# Switcher_Charger.net
KiCad netlist of a schematic drawn in Altium Designer
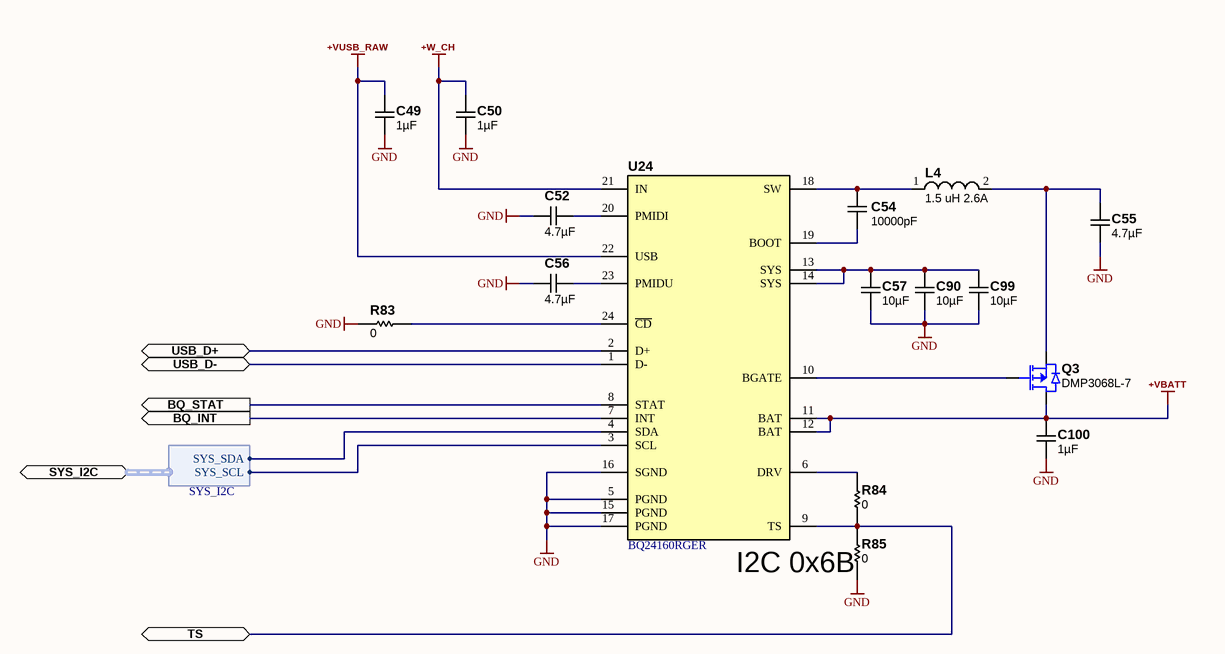
[diagram p0: Switcher_Charger.SchDoc]

(export (version "E")
  (design (tool "Eeschema 10.0.6"))
  (components
    (comp (ref "C49")
      (value "1µF")
      (footprint "C0603_0.90MM_MD")
      (description "CAP CER 1UF 16V X7R 0603")
      (fields
        (field (name "MANUFACTURER PART NUMBER") "CGA3E1X7R1C105K080AC")
        (field (name "MANUFACTURER") "TDK Corporation")
      )
      (libsource (lib "Capacitors - TDK- AEC-Q200") (part "C_2P_NP"))
    )
    (comp (ref "C50")
      (value "1µF")
      (footprint "C0603_0.90MM_MD")
      (description "CAP CER 1UF 16V X7R 0603")
      (fields
        (field (name "MANUFACTURER PART NUMBER") "CGA3E1X7R1C105K080AC")
        (field (name "MANUFACTURER") "TDK Corporation")
      )
      (libsource (lib "Capacitors - TDK- AEC-Q200") (part "C_2P_NP"))
    )
    (comp (ref "C52")
      (value "4.7µF")
      (footprint "C0805_1.45MM_MD")
      (description "CAP CER 4.7UF 16V X7R 0805")
      (fields
        (field (name "MANUFACTURER PART NUMBER") "CGA4J3X7R1C475K125AB")
        (field (name "MANUFACTURER") "TDK Corporation")
      )
      (libsource (lib "Capacitors - TDK- AEC-Q200") (part "C_2P_NP"))
    )
    (comp (ref "C54")
      (value "10000pF")
      (footprint "C0603_0.90MM_MD")
      (description "CAP CER 10000PF 50V C0G 0603")
      (fields
        (field (name "MANUFACTURER PART NUMBER") "CGA3E2C0G1H103J080AA")
        (field (name "MANUFACTURER") "TDK Corporation")
      )
      (libsource (lib "Capacitors - TDK- AEC-Q200") (part "C_2P_NP"))
    )
    (comp (ref "C55")
      (value "4.7µF")
      (footprint "C0805_1.45MM_MD")
      (description "CAP CER 4.7UF 16V X7R 0805")
      (fields
        (field (name "MANUFACTURER PART NUMBER") "CGA4J3X7R1C475K125AB")
        (field (name "MANUFACTURER") "TDK Corporation")
      )
      (libsource (lib "Capacitors - TDK- AEC-Q200") (part "C_2P_NP"))
    )
    (comp (ref "C56")
      (value "4.7µF")
      (footprint "C0805_1.45MM_MD")
      (description "CAP CER 4.7UF 16V X7R 0805")
      (fields
        (field (name "MANUFACTURER PART NUMBER") "CGA4J3X7R1C475K125AB")
        (field (name "MANUFACTURER") "TDK Corporation")
      )
      (libsource (lib "Capacitors - TDK- AEC-Q200") (part "C_2P_NP"))
    )
    (comp (ref "C57")
      (value "10µF")
      (footprint "C0805_1.40MM_MD")
      (description "CAP CER 10UF 10V X7R 0805")
      (fields
        (field (name "MANUFACTURER PART NUMBER") "GCM21BR71A106KE22L")
        (field (name "MANUFACTURER") "Murata Electronics")
      )
      (libsource (lib "Capacitors - Murata - AEC-Q200") (part "C_2P_NP"))
    )
    (comp (ref "C90")
      (value "10µF")
      (footprint "C0805_1.40MM_MD")
      (description "CAP CER 10UF 10V X7R 0805")
      (fields
        (field (name "MANUFACTURER PART NUMBER") "GCM21BR71A106KE22L")
        (field (name "MANUFACTURER") "Murata Electronics")
      )
      (libsource (lib "Capacitors - Murata - AEC-Q200") (part "C_2P_NP"))
    )
    (comp (ref "C99")
      (value "10µF")
      (footprint "C0805_1.40MM_MD")
      (description "CAP CER 10UF 10V X7R 0805")
      (fields
        (field (name "MANUFACTURER PART NUMBER") "GCM21BR71A106KE22L")
        (field (name "MANUFACTURER") "Murata Electronics")
      )
      (libsource (lib "Capacitors - Murata - AEC-Q200") (part "C_2P_NP"))
    )
    (comp (ref "C100")
      (value "1µF")
      (footprint "C0603_0.90MM_MD")
      (description "CAP CER 1UF 16V X7R 0603")
      (fields
        (field (name "MANUFACTURER PART NUMBER") "CGA3E1X7R1C105K080AC")
        (field (name "MANUFACTURER") "TDK Corporation")
      )
      (libsource (lib "Capacitors - TDK- AEC-Q200") (part "C_2P_NP"))
    )
    (comp (ref "L4")
      (value "1.5 uH 2.6A")
      (footprint "L_DO1608C")
      (fields
        (field (name "MANUFACTURER PART NUMBER") "DO1608C-152ML")
        (field (name "MANUFACTURER") "Coilcraft")
        (field (name "PART NUMBER") "DO1608C-152ML_")
      )
      (libsource (lib "Inductors") (part "L_2P"))
    )
    (comp (ref "Q3")
      (value "DMP3068L-7")
      (footprint "SOT-23")
      (description "MOSFET P-CH 30V 3.9A SOT23")
      (fields (field (name "MANUFACTURER") "Diodes"))
      (libsource (lib "eTransistor") (part "DMP3068L-7"))
    )
    (comp (ref "R83")
      (value "0")
      (footprint "R0603_0.55MM_MD")
      (description "RES 0.0 OHM 1/10W JUMP 0603 SMD")
      (fields
        (field (name "MANUFACTURER PART NUMBER") "ERJ-3GEY0R00V")
        (field (name "MANUFACTURER") "Panasonic Electronic Components")
      )
      (libsource (lib "Resistors - Panasonic - AEC-Q200") (part "R_2P"))
    )
    (comp (ref "R84")
      (value "0")
      (footprint "R0603_0.55MM_MD")
      (description "RES 0.0 OHM 1/10W JUMP 0603 SMD")
      (fields
        (field (name "MANUFACTURER PART NUMBER") "ERJ-3GEY0R00V")
        (field (name "MANUFACTURER") "Panasonic Electronic Components")
      )
      (libsource (lib "Resistors - Panasonic - AEC-Q200") (part "R_2P"))
    )
    (comp (ref "R85")
      (value "0")
      (footprint "R0603_0.55MM_MD")
      (description "RES 0.0 OHM 1/10W JUMP 0603 SMD")
      (fields
        (field (name "MANUFACTURER PART NUMBER") "ERJ-3GEY0R00V")
        (field (name "MANUFACTURER") "Panasonic Electronic Components")
      )
      (libsource (lib "Resistors - Panasonic - AEC-Q200") (part "R_2P"))
    )
    (comp (ref "U24")
      (value "BQ24160RGER")
      (footprint "QFN50P400X400X100_HS-25N")
      (description "Switching Battery Charger Li-Ion 2500mA 3.5V to 4.44V 24-Pin VQFN EP T/R")
      (fields (field (name "MANUFACTURER") "Texas Instruments"))
      (libsource (lib "eIC_BatteryManagement") (part "BQ24160RGER"))
    )
  )
  (nets
    (net (code "2") (name "+VBATT") (class "Default")
      (node (ref "C100") (pin "2") (pinfunction "1_2") (pintype "passive"))
      (node (ref "Q3") (pin "3") (pinfunction "D_3") (pintype "passive"))
      (node (ref "U24") (pin "11") (pinfunction "BAT_11") (pintype "passive"))
      (node (ref "U24") (pin "12") (pinfunction "BAT_12") (pintype "passive"))
    )
    (net (code "3") (name "+VUSB_RAW") (class "Default")
      (node (ref "C49") (pin "2") (pinfunction "1_2") (pintype "passive"))
      (node (ref "U24") (pin "22") (pinfunction "USB_22") (pintype "passive"))
    )
    (net (code "4") (name "+W_CH") (class "Default")
      (node (ref "C50") (pin "2") (pinfunction "1_2") (pintype "passive"))
      (node (ref "U24") (pin "21") (pinfunction "IN_21") (pintype "passive"))
    )
    (net (code "5") (name "/BQ_INT") (class "Default")
      (node (ref "U24") (pin "7") (pinfunction "INT_7") (pintype "passive"))
    )
    (net (code "6") (name "/BQ_STAT") (class "Default")
      (node (ref "U24") (pin "8") (pinfunction "STAT_8") (pintype "passive"))
    )
    (net (code "7") (name "/SYS_SCL") (class "Default")
      (node (ref "U24") (pin "3") (pinfunction "SCL_3") (pintype "passive"))
    )
    (net (code "8") (name "/SYS_SDA") (class "Default")
      (node (ref "U24") (pin "4") (pinfunction "SDA_4") (pintype "passive"))
    )
    (net (code "9") (name "/TS") (class "Default")
      (node (ref "R84") (pin "1") (pinfunction "1_1") (pintype "passive"))
      (node (ref "R85") (pin "2") (pinfunction "2_2") (pintype "passive"))
      (node (ref "U24") (pin "9") (pinfunction "TS_9") (pintype "passive"))
    )
    (net (code "10") (name "/USB_D+") (class "Default")
      (node (ref "U24") (pin "2") (pinfunction "D+_2") (pintype "passive"))
    )
    (net (code "11") (name "/USB_D-") (class "Default")
      (node (ref "U24") (pin "1") (pinfunction "D-_1") (pintype "passive"))
    )
    (net (code "13") (name "GND") (class "Default")
      (node (ref "C100") (pin "1") (pinfunction "1_1") (pintype "passive"))
      (node (ref "C49") (pin "1") (pinfunction "1_1") (pintype "passive"))
      (node (ref "C50") (pin "1") (pinfunction "1_1") (pintype "passive"))
      (node (ref "C52") (pin "2") (pinfunction "1_2") (pintype "passive"))
      (node (ref "C55") (pin "1") (pinfunction "1_1") (pintype "passive"))
      (node (ref "C56") (pin "2") (pinfunction "1_2") (pintype "passive"))
      (node (ref "C57") (pin "1") (pinfunction "1_1") (pintype "passive"))
      (node (ref "C90") (pin "1") (pinfunction "1_1") (pintype "passive"))
      (node (ref "C99") (pin "1") (pinfunction "1_1") (pintype "passive"))
      (node (ref "R83") (pin "2") (pinfunction "2_2") (pintype "passive"))
      (node (ref "R85") (pin "1") (pinfunction "1_1") (pintype "passive"))
      (node (ref "U24") (pin "15") (pinfunction "PGND_15") (pintype "passive"))
      (node (ref "U24") (pin "16") (pinfunction "SGND_16") (pintype "passive"))
      (node (ref "U24") (pin "17") (pinfunction "PGND_17") (pintype "passive"))
      (node (ref "U24") (pin "5") (pinfunction "PGND_5") (pintype "passive"))
    )
    (net (code "14") (name "Net-(C57-1-Pad2)") (class "Default")
      (node (ref "C57") (pin "2") (pinfunction "1_2") (pintype "passive"))
      (node (ref "C90") (pin "2") (pinfunction "1_2") (pintype "passive"))
      (node (ref "C99") (pin "2") (pinfunction "1_2") (pintype "passive"))
      (node (ref "U24") (pin "13") (pinfunction "SYS_13") (pintype "passive"))
      (node (ref "U24") (pin "14") (pinfunction "SYS_14") (pintype "passive"))
    )
    (net (code "15") (name "Net-(Q3-G)") (class "Default")
      (node (ref "Q3") (pin "1") (pinfunction "G_1") (pintype "passive"))
      (node (ref "U24") (pin "10") (pinfunction "BGATE_10") (pintype "passive"))
    )
    (net (code "16") (name "Net-(Q3-S)") (class "Default")
      (node (ref "C55") (pin "2") (pinfunction "1_2") (pintype "passive"))
      (node (ref "L4") (pin "2") (pinfunction "2_2") (pintype "passive"))
      (node (ref "Q3") (pin "2") (pinfunction "S_2") (pintype "passive"))
    )
    (net (code "17") (name "Net-(U24-BOOT)") (class "Default")
      (node (ref "C54") (pin "1") (pinfunction "1_1") (pintype "passive"))
      (node (ref "U24") (pin "19") (pinfunction "BOOT_19") (pintype "passive"))
    )
    (net (code "18") (name "Net-(U24-DRV)") (class "Default")
      (node (ref "R84") (pin "2") (pinfunction "2_2") (pintype "passive"))
      (node (ref "U24") (pin "6") (pinfunction "DRV_6") (pintype "passive"))
    )
    (net (code "19") (name "Net-(U24-PMIDI)") (class "Default")
      (node (ref "C52") (pin "1") (pinfunction "1_1") (pintype "passive"))
      (node (ref "U24") (pin "20") (pinfunction "PMIDI_20") (pintype "passive"))
    )
    (net (code "20") (name "Net-(U24-PMIDU)") (class "Default")
      (node (ref "C56") (pin "1") (pinfunction "1_1") (pintype "passive"))
      (node (ref "U24") (pin "23") (pinfunction "PMIDU_23") (pintype "passive"))
    )
    (net (code "21") (name "Net-(U24-SW)") (class "Default")
      (node (ref "C54") (pin "2") (pinfunction "1_2") (pintype "passive"))
      (node (ref "L4") (pin "1") (pinfunction "1_1") (pintype "passive"))
      (node (ref "U24") (pin "18") (pinfunction "SW_18") (pintype "passive"))
    )
    (net (code "22") (name "Net-(U24-~{CD})") (class "Default")
      (node (ref "R83") (pin "1") (pinfunction "1_1") (pintype "passive"))
      (node (ref "U24") (pin "24") (pinfunction "~{CD}_24") (pintype "passive"))
    )
  )
)
